# PuM_Arduino_Shield_v2.net
KiCad netlist of a schematic drawn in EAGLE
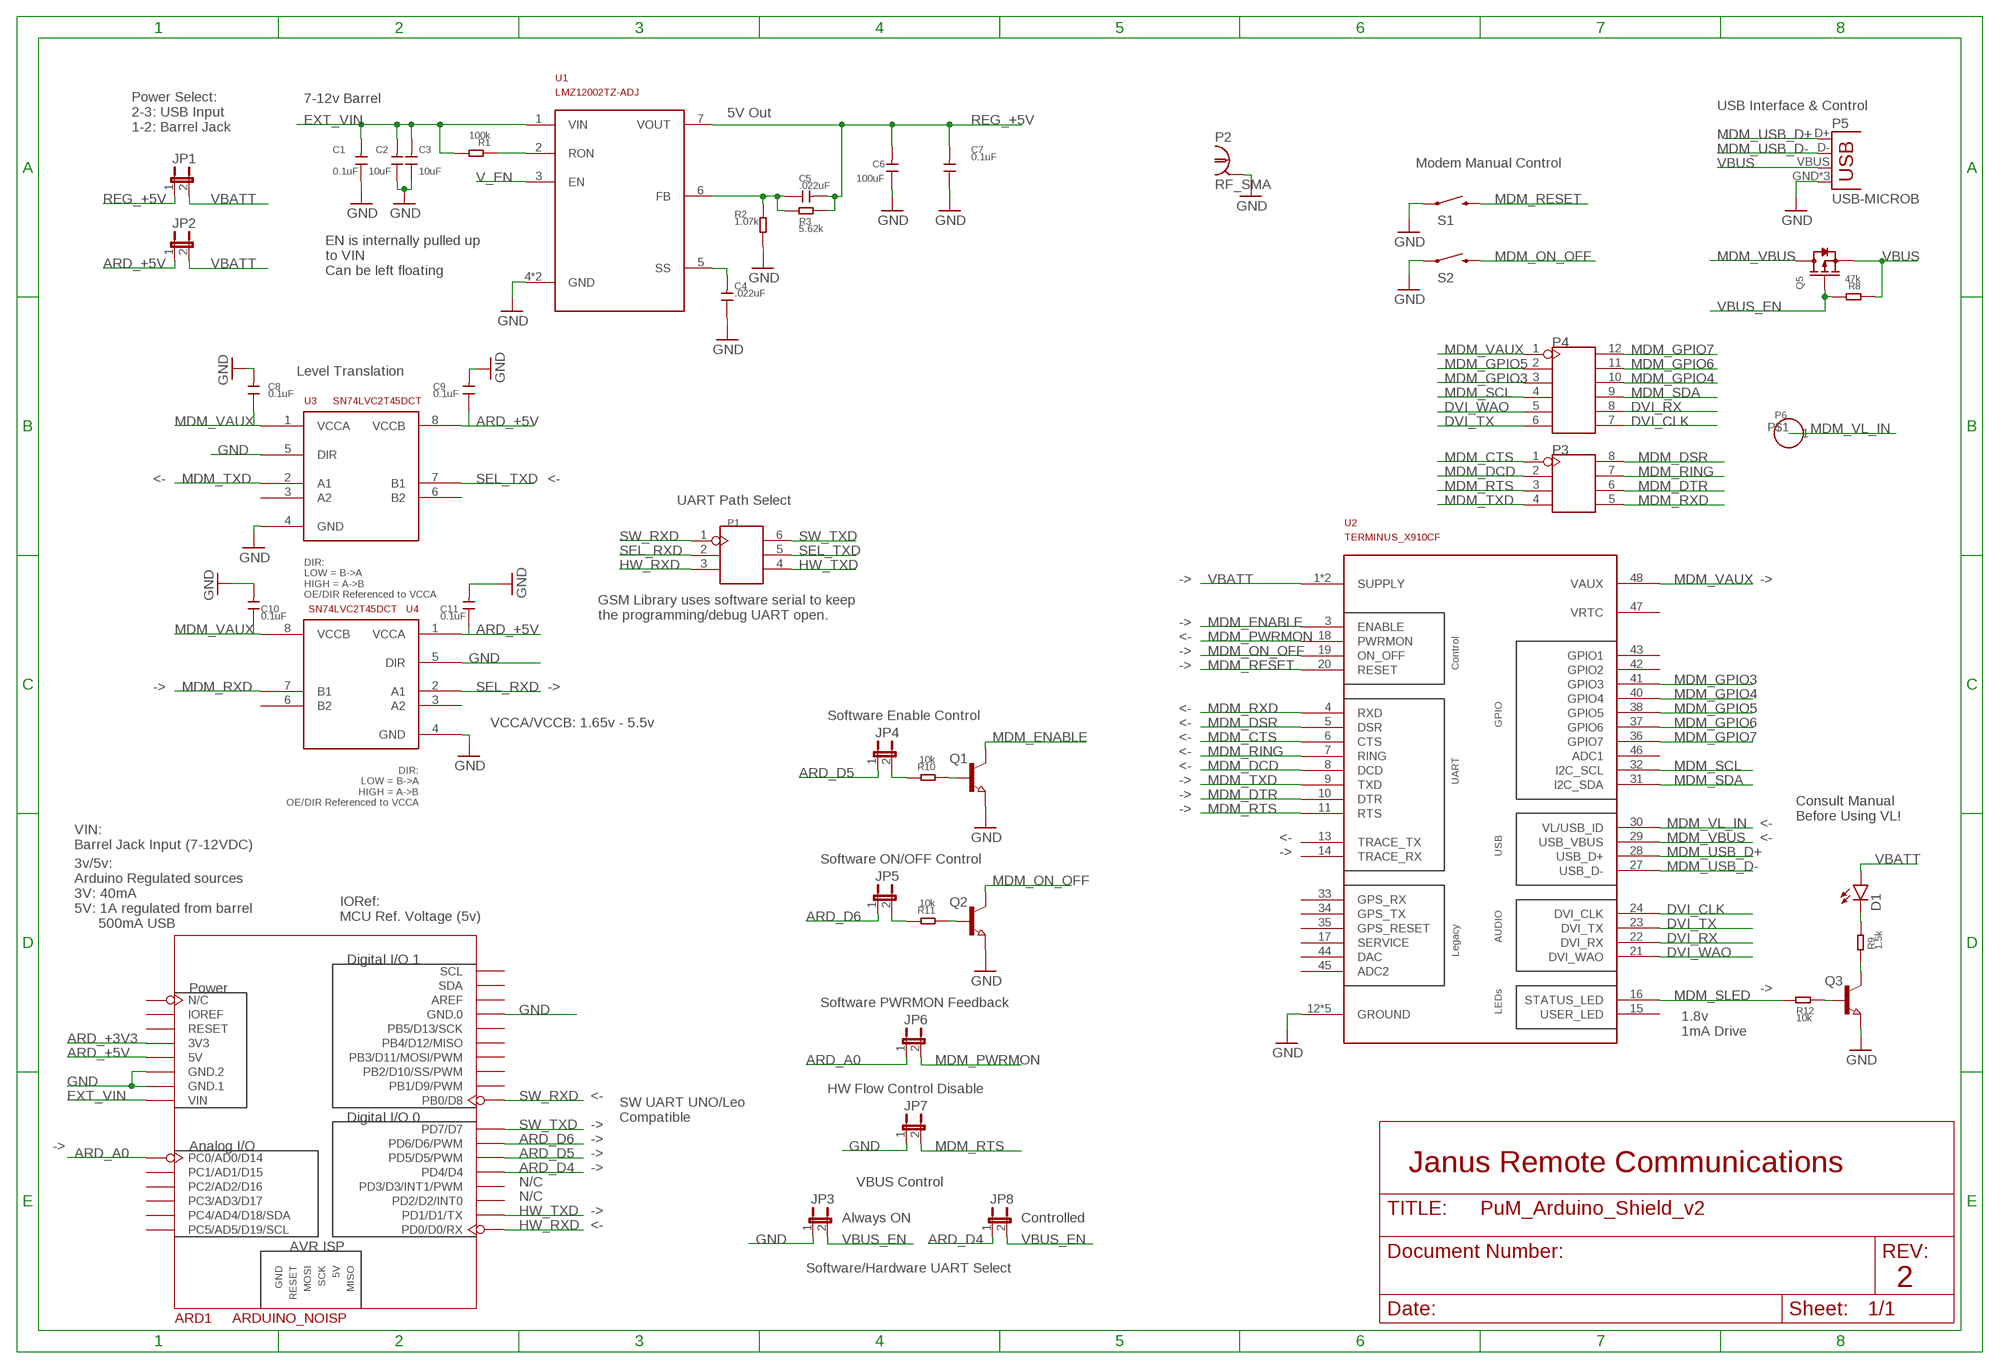
[diagram p0: schematic, sheet 1]

(export (version "E")
  (design (tool "Eeschema 10.0.6"))
  (components
    (comp (ref "ARD1")
      (value "ARDUINO_NOISP")
      (footprint "eagle-import:ARDUINO_NOISP")
      (libsource (lib "eagle-import") (part "ARDUINO_NOISP"))
    )
    (comp (ref "C1")
      (value "0.1uF")
      (footprint "eagle-import:C0402")
      (libsource (lib "eagle-import") (part "C-0402"))
    )
    (comp (ref "C2")
      (value "10uF")
      (footprint "eagle-import:C0805")
      (libsource (lib "eagle-import") (part "C-0805"))
    )
    (comp (ref "C3")
      (value "10uF")
      (footprint "eagle-import:C0805")
      (libsource (lib "eagle-import") (part "C-0805"))
    )
    (comp (ref "C4")
      (value ".022uF")
      (footprint "eagle-import:C0402")
      (libsource (lib "eagle-import") (part "C-0402"))
    )
    (comp (ref "C5")
      (value ".022uF")
      (footprint "eagle-import:C0402")
      (libsource (lib "eagle-import") (part "C-0402"))
    )
    (comp (ref "C6")
      (value "100uF")
      (footprint "eagle-import:C1206")
      (libsource (lib "eagle-import") (part "C-1206"))
    )
    (comp (ref "C7")
      (value "0.1uF")
      (footprint "eagle-import:C0402")
      (libsource (lib "eagle-import") (part "C-0402"))
    )
    (comp (ref "C8")
      (value "0.1uF")
      (footprint "eagle-import:C0402")
      (libsource (lib "eagle-import") (part "C-0402"))
    )
    (comp (ref "C9")
      (value "0.1uF")
      (footprint "eagle-import:C0402")
      (libsource (lib "eagle-import") (part "C-0402"))
    )
    (comp (ref "C10")
      (value "0.1uF")
      (footprint "eagle-import:C0402")
      (libsource (lib "eagle-import") (part "C-0402"))
    )
    (comp (ref "C11")
      (value "0.1uF")
      (footprint "eagle-import:C0402")
      (libsource (lib "eagle-import") (part "C-0402"))
    )
    (comp (ref "D1")
      (value "LED0603")
      (footprint "eagle-import:LED-0603")
      (libsource (lib "eagle-import") (part "LED0603"))
    )
    (comp (ref "JP1")
      (value "JUMPER-2SMD-NC")
      (footprint "eagle-import:SJ_2S")
      (libsource (lib "eagle-import") (part "JUMPER-2SMD-NC"))
    )
    (comp (ref "JP2")
      (value "JUMPER-2SMD-NO")
      (footprint "eagle-import:SJ_2S-NO")
      (libsource (lib "eagle-import") (part "JUMPER-2SMD-NO"))
    )
    (comp (ref "JP3")
      (value "JUMPER-2SMD-NO")
      (footprint "eagle-import:SJ_2S-NO")
      (libsource (lib "eagle-import") (part "JUMPER-2SMD-NO"))
    )
    (comp (ref "JP4")
      (value "JUMPER-2SMD-NC")
      (footprint "eagle-import:SJ_2S")
      (libsource (lib "eagle-import") (part "JUMPER-2SMD-NC"))
    )
    (comp (ref "JP5")
      (value "JUMPER-2SMD-NC")
      (footprint "eagle-import:SJ_2S")
      (libsource (lib "eagle-import") (part "JUMPER-2SMD-NC"))
    )
    (comp (ref "JP6")
      (value "JUMPER-2SMD-NC")
      (footprint "eagle-import:SJ_2S")
      (libsource (lib "eagle-import") (part "JUMPER-2SMD-NC"))
    )
    (comp (ref "JP7")
      (value "JUMPER-2SMD-NC")
      (footprint "eagle-import:SJ_2S")
      (libsource (lib "eagle-import") (part "JUMPER-2SMD-NC"))
    )
    (comp (ref "JP8")
      (value "JUMPER-2SMD-NC")
      (footprint "eagle-import:SJ_2S")
      (libsource (lib "eagle-import") (part "JUMPER-2SMD-NC"))
    )
    (comp (ref "P1")
      (value "HEADER-2X3P-2.54")
      (footprint "eagle-import:2X3P-2.54")
      (libsource (lib "eagle-import") (part "HEADER-2X3P-2.54"))
    )
    (comp (ref "P2")
      (value "RF_SMA")
      (footprint "eagle-import:RF_SMA_NOPIN")
      (libsource (lib "eagle-import") (part "RF_SMA"))
    )
    (comp (ref "P3")
      (value "HEADER-2X4P-2.54")
      (footprint "eagle-import:2X4P-2.54")
      (libsource (lib "eagle-import") (part "HEADER-2X4P-2.54"))
    )
    (comp (ref "P4")
      (value "HEADER-2X6P-2.54")
      (footprint "eagle-import:2X6P-2.54")
      (libsource (lib "eagle-import") (part "HEADER-2X6P-2.54"))
    )
    (comp (ref "P5")
      (value "USB-MICROB")
      (footprint "eagle-import:USB-MICROB")
      (libsource (lib "eagle-import") (part "USB-MICROB"))
    )
    (comp (ref "P6")
      (value "HEADER-1P-35")
      (footprint "eagle-import:1P-65_35MIL")
      (libsource (lib "eagle-import") (part "HEADER-1P-35"))
    )
    (comp (ref "Q1")
      (value "NPN-TRANSISTOR_SOT23")
      (footprint "eagle-import:SOT23")
      (libsource (lib "eagle-import") (part "NPN-TRANSISTOR_SOT23"))
    )
    (comp (ref "Q2")
      (value "NPN-TRANSISTOR_SOT23")
      (footprint "eagle-import:SOT23")
      (libsource (lib "eagle-import") (part "NPN-TRANSISTOR_SOT23"))
    )
    (comp (ref "Q3")
      (value "NPN-TRANSISTOR_SOT23")
      (footprint "eagle-import:SOT23")
      (libsource (lib "eagle-import") (part "NPN-TRANSISTOR_SOT23"))
    )
    (comp (ref "Q5")
      (value "MOSFET-P'SI2323CDS/SI2305DS<BR>'")
      (footprint "eagle-import:SOT23")
      (libsource (lib "eagle-import") (part "MOSFET-P'SI2323CDS/SI2305DS{lt}BR{gt}'"))
    )
    (comp (ref "R1")
      (value "100k")
      (footprint "eagle-import:R0402")
      (libsource (lib "eagle-import") (part "R-0402"))
    )
    (comp (ref "R2")
      (value "1.07k")
      (footprint "eagle-import:R0402")
      (libsource (lib "eagle-import") (part "R-0402"))
    )
    (comp (ref "R3")
      (value "5.62k")
      (footprint "eagle-import:R0402")
      (libsource (lib "eagle-import") (part "R-0402"))
    )
    (comp (ref "R8")
      (value "47k")
      (footprint "eagle-import:R0402")
      (libsource (lib "eagle-import") (part "R-0402"))
    )
    (comp (ref "R9")
      (value "1.5k")
      (footprint "eagle-import:R0402")
      (libsource (lib "eagle-import") (part "R-0402"))
    )
    (comp (ref "R10")
      (value "10k")
      (footprint "eagle-import:R0402")
      (libsource (lib "eagle-import") (part "R-0402"))
    )
    (comp (ref "R11")
      (value "10k")
      (footprint "eagle-import:R0402")
      (libsource (lib "eagle-import") (part "R-0402"))
    )
    (comp (ref "R12")
      (value "10k")
      (footprint "eagle-import:R0402")
      (libsource (lib "eagle-import") (part "R-0402"))
    )
    (comp (ref "S1")
      (value "SWITCH-MOMENTARY-2SIDE_EZ")
      (footprint "eagle-import:TACTILE-PTH-SIDEEZ")
      (libsource (lib "eagle-import") (part "SWITCH-MOMENTARY-2SIDE_EZ"))
    )
    (comp (ref "S2")
      (value "SWITCH-MOMENTARY-2SIDE_EZ")
      (footprint "eagle-import:TACTILE-PTH-SIDEEZ")
      (libsource (lib "eagle-import") (part "SWITCH-MOMENTARY-2SIDE_EZ"))
    )
    (comp (ref "U1")
      (value "LMZ12002TZ-ADJ")
      (footprint "eagle-import:TO-PMOD-7")
      (libsource (lib "eagle-import") (part "LMZ12002TZ-ADJ"))
    )
    (comp (ref "U2")
      (value "TERMINUS_X910CF")
      (footprint "eagle-import:X910CF")
      (libsource (lib "eagle-import") (part "TERMINUS_X910CF"))
    )
    (comp (ref "U3")
      (value "SN74LVC2T45DCT")
      (footprint "eagle-import:LSSOP-8")
      (libsource (lib "eagle-import") (part "SN74LVC2T45DCT"))
    )
    (comp (ref "U4")
      (value "SN74LVC2T45DCT")
      (footprint "eagle-import:LSSOP-8")
      (libsource (lib "eagle-import") (part "SN74LVC2T45DCT"))
    )
  )
  (nets
    (net (code "1") (name "/ARD_+3V3") (class "Default")
      (node (ref "ARD1") (pin "3V3") (pinfunction "3V3_3V3") (pintype "bidirectional"))
    )
    (net (code "2") (name "/ARD_+5V") (class "Default")
      (node (ref "ARD1") (pin "5V") (pinfunction "5V_5V") (pintype "bidirectional"))
      (node (ref "C11") (pin "1") (pinfunction "1_1") (pintype "passive"))
      (node (ref "C9") (pin "1") (pinfunction "1_1") (pintype "passive"))
      (node (ref "JP2") (pin "1") (pinfunction "1_1") (pintype "passive"))
      (node (ref "U3") (pin "8") (pinfunction "VCCB_8") (pintype "bidirectional"))
      (node (ref "U4") (pin "1") (pinfunction "VCCA_1") (pintype "bidirectional"))
    )
    (net (code "3") (name "/ARD_A0") (class "Default")
      (node (ref "ARD1") (pin "A0") (pinfunction "PC0/AD0/D14_A0") (pintype "bidirectional"))
      (node (ref "JP6") (pin "1") (pinfunction "1_1") (pintype "passive"))
    )
    (net (code "4") (name "/ARD_D4") (class "Default")
      (node (ref "ARD1") (pin "D4") (pinfunction "PD4/D4_D4") (pintype "bidirectional"))
      (node (ref "JP8") (pin "1") (pinfunction "1_1") (pintype "passive"))
    )
    (net (code "5") (name "/ARD_D5") (class "Default")
      (node (ref "ARD1") (pin "D5") (pinfunction "PD5/D5/PWM_D5") (pintype "bidirectional"))
      (node (ref "JP4") (pin "1") (pinfunction "1_1") (pintype "passive"))
    )
    (net (code "6") (name "/ARD_D6") (class "Default")
      (node (ref "ARD1") (pin "D6") (pinfunction "PD6/D6/PWM_D6") (pintype "bidirectional"))
      (node (ref "JP5") (pin "1") (pinfunction "1_1") (pintype "passive"))
    )
    (net (code "7") (name "/DVI_CLK") (class "Default")
      (node (ref "P4") (pin "7") (pinfunction "7_7") (pintype "bidirectional"))
      (node (ref "U2") (pin "24") (pinfunction "DVI_CLK_24") (pintype "bidirectional"))
    )
    (net (code "8") (name "/DVI_RX") (class "Default")
      (node (ref "P4") (pin "8") (pinfunction "8_8") (pintype "bidirectional"))
      (node (ref "U2") (pin "22") (pinfunction "DVI_RX_22") (pintype "bidirectional"))
    )
    (net (code "9") (name "/DVI_TX") (class "Default")
      (node (ref "P4") (pin "6") (pinfunction "6_6") (pintype "bidirectional"))
      (node (ref "U2") (pin "23") (pinfunction "DVI_TX_23") (pintype "bidirectional"))
    )
    (net (code "10") (name "/DVI_WAO") (class "Default")
      (node (ref "P4") (pin "5") (pinfunction "5_5") (pintype "bidirectional"))
      (node (ref "U2") (pin "21") (pinfunction "DVI_WAO_21") (pintype "bidirectional"))
    )
    (net (code "11") (name "/EXT_VIN") (class "Default")
      (node (ref "ARD1") (pin "VIN") (pinfunction "VIN_VIN") (pintype "bidirectional"))
      (node (ref "C1") (pin "2") (pinfunction "2_2") (pintype "passive"))
      (node (ref "C2") (pin "2") (pinfunction "2_2") (pintype "passive"))
      (node (ref "C3") (pin "2") (pinfunction "2_2") (pintype "passive"))
      (node (ref "R1") (pin "2") (pinfunction "2_2") (pintype "passive"))
      (node (ref "U1") (pin "1") (pinfunction "VIN_1") (pintype "bidirectional"))
    )
    (net (code "12") (name "/HW_RXD") (class "Default")
      (node (ref "ARD1") (pin "D0") (pinfunction "PD0/D0/RX_D0") (pintype "bidirectional"))
      (node (ref "P1") (pin "3") (pinfunction "3_3") (pintype "bidirectional"))
    )
    (net (code "13") (name "/HW_TXD") (class "Default")
      (node (ref "ARD1") (pin "D1") (pinfunction "PD1/D1/TX_D1") (pintype "bidirectional"))
      (node (ref "P1") (pin "4") (pinfunction "4_4") (pintype "bidirectional"))
    )
    (net (code "14") (name "/MDM_CTS") (class "Default")
      (node (ref "P3") (pin "1") (pinfunction "1_1") (pintype "bidirectional"))
      (node (ref "U2") (pin "6") (pinfunction "CTS_6") (pintype "bidirectional"))
    )
    (net (code "15") (name "/MDM_DCD") (class "Default")
      (node (ref "P3") (pin "2") (pinfunction "2_2") (pintype "bidirectional"))
      (node (ref "U2") (pin "8") (pinfunction "DCD_8") (pintype "bidirectional"))
    )
    (net (code "16") (name "/MDM_DSR") (class "Default")
      (node (ref "P3") (pin "8") (pinfunction "8_8") (pintype "bidirectional"))
      (node (ref "U2") (pin "5") (pinfunction "DSR_5") (pintype "bidirectional"))
    )
    (net (code "17") (name "/MDM_DTR") (class "Default")
      (node (ref "P3") (pin "6") (pinfunction "6_6") (pintype "bidirectional"))
      (node (ref "U2") (pin "10") (pinfunction "DTR_10") (pintype "bidirectional"))
    )
    (net (code "18") (name "/MDM_ENABLE") (class "Default")
      (node (ref "Q1") (pin "3") (pinfunction "C_3") (pintype "passive"))
      (node (ref "U2") (pin "3") (pinfunction "ENABLE_3") (pintype "bidirectional"))
    )
    (net (code "19") (name "/MDM_GPIO3") (class "Default")
      (node (ref "P4") (pin "3") (pinfunction "3_3") (pintype "bidirectional"))
      (node (ref "U2") (pin "41") (pinfunction "GPIO3_41") (pintype "bidirectional"))
    )
    (net (code "20") (name "/MDM_GPIO4") (class "Default")
      (node (ref "P4") (pin "10") (pinfunction "10_10") (pintype "bidirectional"))
      (node (ref "U2") (pin "40") (pinfunction "GPIO4_40") (pintype "bidirectional"))
    )
    (net (code "21") (name "/MDM_GPIO5") (class "Default")
      (node (ref "P4") (pin "2") (pinfunction "2_2") (pintype "bidirectional"))
      (node (ref "U2") (pin "38") (pinfunction "GPIO5_38") (pintype "bidirectional"))
    )
    (net (code "22") (name "/MDM_GPIO6") (class "Default")
      (node (ref "P4") (pin "11") (pinfunction "11_11") (pintype "bidirectional"))
      (node (ref "U2") (pin "37") (pinfunction "GPIO6_37") (pintype "bidirectional"))
    )
    (net (code "23") (name "/MDM_GPIO7") (class "Default")
      (node (ref "P4") (pin "12") (pinfunction "12_12") (pintype "bidirectional"))
      (node (ref "U2") (pin "36") (pinfunction "GPIO7_36") (pintype "bidirectional"))
    )
    (net (code "24") (name "/MDM_ON_OFF") (class "Default")
      (node (ref "Q2") (pin "3") (pinfunction "C_3") (pintype "passive"))
      (node (ref "S2") (pin "2") (pinfunction "2_2") (pintype "passive"))
      (node (ref "U2") (pin "19") (pinfunction "ON_OFF_19") (pintype "bidirectional"))
    )
    (net (code "25") (name "/MDM_PWRMON") (class "Default")
      (node (ref "JP6") (pin "2") (pinfunction "2_2") (pintype "passive"))
      (node (ref "U2") (pin "18") (pinfunction "PWRMON_18") (pintype "bidirectional"))
    )
    (net (code "26") (name "/MDM_RESET") (class "Default")
      (node (ref "S1") (pin "2") (pinfunction "2_2") (pintype "passive"))
      (node (ref "U2") (pin "20") (pinfunction "RESET_20") (pintype "bidirectional"))
    )
    (net (code "27") (name "/MDM_RING") (class "Default")
      (node (ref "P3") (pin "7") (pinfunction "7_7") (pintype "bidirectional"))
      (node (ref "U2") (pin "7") (pinfunction "RING_7") (pintype "bidirectional"))
    )
    (net (code "28") (name "/MDM_RTS") (class "Default")
      (node (ref "JP7") (pin "2") (pinfunction "2_2") (pintype "passive"))
      (node (ref "P3") (pin "3") (pinfunction "3_3") (pintype "bidirectional"))
      (node (ref "U2") (pin "11") (pinfunction "RTS_11") (pintype "bidirectional"))
    )
    (net (code "29") (name "/MDM_RXD") (class "Default")
      (node (ref "P3") (pin "5") (pinfunction "5_5") (pintype "bidirectional"))
      (node (ref "U2") (pin "4") (pinfunction "RXD_4") (pintype "bidirectional"))
      (node (ref "U4") (pin "7") (pinfunction "B1_7") (pintype "bidirectional"))
    )
    (net (code "30") (name "/MDM_SCL") (class "Default")
      (node (ref "P4") (pin "4") (pinfunction "4_4") (pintype "bidirectional"))
      (node (ref "U2") (pin "32") (pinfunction "I2C_SCL_32") (pintype "bidirectional"))
    )
    (net (code "31") (name "/MDM_SDA") (class "Default")
      (node (ref "P4") (pin "9") (pinfunction "9_9") (pintype "bidirectional"))
      (node (ref "U2") (pin "31") (pinfunction "I2C_SDA_31") (pintype "bidirectional"))
    )
    (net (code "32") (name "/MDM_SLED") (class "Default")
      (node (ref "R12") (pin "2") (pinfunction "2_2") (pintype "passive"))
      (node (ref "U2") (pin "16") (pinfunction "STATUS_LED_16") (pintype "bidirectional"))
    )
    (net (code "33") (name "/MDM_TXD") (class "Default")
      (node (ref "P3") (pin "4") (pinfunction "4_4") (pintype "bidirectional"))
      (node (ref "U2") (pin "9") (pinfunction "TXD_9") (pintype "bidirectional"))
      (node (ref "U3") (pin "2") (pinfunction "A1_2") (pintype "bidirectional"))
    )
    (net (code "34") (name "/MDM_USB_D+") (class "Default")
      (node (ref "P5") (pin "D+") (pinfunction "D+_D+") (pintype "bidirectional"))
      (node (ref "U2") (pin "28") (pinfunction "USB_D+_28") (pintype "bidirectional"))
    )
    (net (code "35") (name "/MDM_USB_D-") (class "Default")
      (node (ref "P5") (pin "D-") (pinfunction "D-_D-") (pintype "bidirectional"))
      (node (ref "U2") (pin "27") (pinfunction "USB_D-_27") (pintype "bidirectional"))
    )
    (net (code "36") (name "/MDM_VAUX") (class "Default")
      (node (ref "C10") (pin "1") (pinfunction "1_1") (pintype "passive"))
      (node (ref "C8") (pin "1") (pinfunction "1_1") (pintype "passive"))
      (node (ref "P4") (pin "1") (pinfunction "1_1") (pintype "bidirectional"))
      (node (ref "U2") (pin "48") (pinfunction "VAUX_48") (pintype "bidirectional"))
      (node (ref "U3") (pin "1") (pinfunction "VCCA_1") (pintype "bidirectional"))
      (node (ref "U4") (pin "8") (pinfunction "VCCB_8") (pintype "bidirectional"))
    )
    (net (code "37") (name "/MDM_VBUS") (class "Default")
      (node (ref "Q5") (pin "3") (pinfunction "D_3") (pintype "passive"))
      (node (ref "U2") (pin "29") (pinfunction "USB_VBUS_29") (pintype "bidirectional"))
    )
    (net (code "38") (name "/MDM_VL_IN") (class "Default")
      (node (ref "P6") (pin "P$1") (pinfunction "1_P$1") (pintype "bidirectional"))
      (node (ref "U2") (pin "30") (pinfunction "VL/USB_ID_30") (pintype "bidirectional"))
    )
    (net (code "39") (name "/REG_+5V") (class "Default")
      (node (ref "C5") (pin "2") (pinfunction "2_2") (pintype "passive"))
      (node (ref "C6") (pin "2") (pinfunction "2_2") (pintype "passive"))
      (node (ref "C7") (pin "2") (pinfunction "2_2") (pintype "passive"))
      (node (ref "JP1") (pin "1") (pinfunction "1_1") (pintype "passive"))
      (node (ref "R3") (pin "1") (pinfunction "1_1") (pintype "passive"))
      (node (ref "U1") (pin "7") (pinfunction "VOUT_7") (pintype "bidirectional"))
    )
    (net (code "40") (name "/SEL_RXD") (class "Default")
      (node (ref "P1") (pin "2") (pinfunction "2_2") (pintype "bidirectional"))
      (node (ref "U4") (pin "2") (pinfunction "A1_2") (pintype "bidirectional"))
    )
    (net (code "41") (name "/SEL_TXD") (class "Default")
      (node (ref "P1") (pin "5") (pinfunction "5_5") (pintype "bidirectional"))
      (node (ref "U3") (pin "7") (pinfunction "B1_7") (pintype "bidirectional"))
    )
    (net (code "42") (name "/SW_RXD") (class "Default")
      (node (ref "ARD1") (pin "D8") (pinfunction "PB0/D8_D8") (pintype "bidirectional"))
      (node (ref "P1") (pin "1") (pinfunction "1_1") (pintype "bidirectional"))
    )
    (net (code "43") (name "/SW_TXD") (class "Default")
      (node (ref "ARD1") (pin "D7") (pinfunction "PD7/D7_D7") (pintype "bidirectional"))
      (node (ref "P1") (pin "6") (pinfunction "6_6") (pintype "bidirectional"))
    )
    (net (code "44") (name "/VBATT") (class "Default")
      (node (ref "D1") (pin "A") (pinfunction "A_A") (pintype "passive"))
      (node (ref "JP1") (pin "2") (pinfunction "2_2") (pintype "passive"))
      (node (ref "JP2") (pin "2") (pinfunction "2_2") (pintype "passive"))
      (node (ref "U2") (pin "1") (pinfunction "SUPPLY_1") (pintype "bidirectional"))
      (node (ref "U2") (pin "2") (pinfunction "SUPPLY_2") (pintype "bidirectional"))
    )
    (net (code "45") (name "/VBUS") (class "Default")
      (node (ref "P5") (pin "VBUS") (pinfunction "VBUS_VBUS") (pintype "bidirectional"))
      (node (ref "Q5") (pin "2") (pinfunction "S_2") (pintype "passive"))
      (node (ref "R8") (pin "2") (pinfunction "2_2") (pintype "passive"))
    )
    (net (code "46") (name "/VBUS_EN") (class "Default")
      (node (ref "JP3") (pin "2") (pinfunction "2_2") (pintype "passive"))
      (node (ref "JP8") (pin "2") (pinfunction "2_2") (pintype "passive"))
      (node (ref "Q5") (pin "1") (pinfunction "G_1") (pintype "passive"))
      (node (ref "R8") (pin "1") (pinfunction "1_1") (pintype "passive"))
    )
    (net (code "47") (name "/V_EN") (class "Default")
      (node (ref "U1") (pin "3") (pinfunction "EN_3") (pintype "bidirectional"))
    )
    (net (code "48") (name "GND") (class "Default")
      (node (ref "ARD1") (pin "GND0") (pinfunction "GND.0_GND0") (pintype "bidirectional"))
      (node (ref "ARD1") (pin "GND1") (pinfunction "GND.1_GND1") (pintype "bidirectional"))
      (node (ref "ARD1") (pin "GND2") (pinfunction "GND.2_GND2") (pintype "bidirectional"))
      (node (ref "C1") (pin "1") (pinfunction "1_1") (pintype "passive"))
      (node (ref "C10") (pin "2") (pinfunction "2_2") (pintype "passive"))
      (node (ref "C11") (pin "2") (pinfunction "2_2") (pintype "passive"))
      (node (ref "C2") (pin "1") (pinfunction "1_1") (pintype "passive"))
      (node (ref "C3") (pin "1") (pinfunction "1_1") (pintype "passive"))
      (node (ref "C4") (pin "1") (pinfunction "1_1") (pintype "passive"))
      (node (ref "C6") (pin "1") (pinfunction "1_1") (pintype "passive"))
      (node (ref "C7") (pin "1") (pinfunction "1_1") (pintype "passive"))
      (node (ref "C8") (pin "2") (pinfunction "2_2") (pintype "passive"))
      (node (ref "C9") (pin "2") (pinfunction "2_2") (pintype "passive"))
      (node (ref "JP3") (pin "1") (pinfunction "1_1") (pintype "passive"))
      (node (ref "JP7") (pin "1") (pinfunction "1_1") (pintype "passive"))
      (node (ref "P2") (pin "2") (pinfunction "2_2") (pintype "passive"))
      (node (ref "P2") (pin "3") (pinfunction "2_3") (pintype "passive"))
      (node (ref "P2") (pin "4") (pinfunction "2_4") (pintype "passive"))
      (node (ref "P2") (pin "5") (pinfunction "2_5") (pintype "passive"))
      (node (ref "P5") (pin "GND") (pinfunction "GND_GND") (pintype "bidirectional"))
      (node (ref "P5") (pin "MT1") (pinfunction "GND_MT1") (pintype "bidirectional"))
      (node (ref "P5") (pin "MT2") (pinfunction "GND_MT2") (pintype "bidirectional"))
      (node (ref "Q1") (pin "2") (pinfunction "E_2") (pintype "passive"))
      (node (ref "Q2") (pin "2") (pinfunction "E_2") (pintype "passive"))
      (node (ref "Q3") (pin "2") (pinfunction "E_2") (pintype "passive"))
      (node (ref "R2") (pin "2") (pinfunction "2_2") (pintype "passive"))
      (node (ref "S1") (pin "1") (pinfunction "1_1") (pintype "passive"))
      (node (ref "S2") (pin "1") (pinfunction "1_1") (pintype "passive"))
      (node (ref "U1") (pin "4") (pinfunction "GND_4") (pintype "bidirectional"))
      (node (ref "U1") (pin "EP") (pinfunction "GND_EP") (pintype "bidirectional"))
      (node (ref "U2") (pin "12") (pinfunction "GROUND_12") (pintype "bidirectional"))
      (node (ref "U2") (pin "25") (pinfunction "GROUND_25") (pintype "bidirectional"))
      (node (ref "U2") (pin "26") (pinfunction "GROUND_26") (pintype "bidirectional"))
      (node (ref "U2") (pin "39") (pinfunction "GROUND_39") (pintype "bidirectional"))
      (node (ref "U2") (pin "49") (pinfunction "GROUND_49") (pintype "bidirectional"))
      (node (ref "U3") (pin "4") (pinfunction "GND_4") (pintype "bidirectional"))
      (node (ref "U3") (pin "5") (pinfunction "DIR_5") (pintype "bidirectional"))
      (node (ref "U4") (pin "4") (pinfunction "GND_4") (pintype "bidirectional"))
      (node (ref "U4") (pin "5") (pinfunction "DIR_5") (pintype "bidirectional"))
    )
    (net (code "49") (name "Net-(D1-PadC)") (class "Default")
      (node (ref "D1") (pin "C") (pinfunction "C_C") (pintype "passive"))
      (node (ref "R9") (pin "1") (pinfunction "1_1") (pintype "passive"))
    )
    (net (code "50") (name "Net-(JP4-Pad2)") (class "Default")
      (node (ref "JP4") (pin "2") (pinfunction "2_2") (pintype "passive"))
      (node (ref "R10") (pin "1") (pinfunction "1_1") (pintype "passive"))
    )
    (net (code "51") (name "Net-(JP5-Pad2)") (class "Default")
      (node (ref "JP5") (pin "2") (pinfunction "2_2") (pintype "passive"))
      (node (ref "R11") (pin "1") (pinfunction "1_1") (pintype "passive"))
    )
    (net (code "52") (name "Net-(Q1-B)") (class "Default")
      (node (ref "Q1") (pin "1") (pinfunction "B_1") (pintype "passive"))
      (node (ref "R10") (pin "2") (pinfunction "2_2") (pintype "passive"))
    )
    (net (code "53") (name "Net-(Q2-B)") (class "Default")
      (node (ref "Q2") (pin "1") (pinfunction "B_1") (pintype "passive"))
      (node (ref "R11") (pin "2") (pinfunction "2_2") (pintype "passive"))
    )
    (net (code "54") (name "Net-(Q3-B)") (class "Default")
      (node (ref "Q3") (pin "1") (pinfunction "B_1") (pintype "passive"))
      (node (ref "R12") (pin "1") (pinfunction "1_1") (pintype "passive"))
    )
    (net (code "55") (name "Net-(Q3-C)") (class "Default")
      (node (ref "Q3") (pin "3") (pinfunction "C_3") (pintype "passive"))
      (node (ref "R9") (pin "2") (pinfunction "2_2") (pintype "passive"))
    )
    (net (code "56") (name "Net-(U1-FB)") (class "Default")
      (node (ref "C5") (pin "1") (pinfunction "1_1") (pintype "passive"))
      (node (ref "R2") (pin "1") (pinfunction "1_1") (pintype "passive"))
      (node (ref "R3") (pin "2") (pinfunction "2_2") (pintype "passive"))
      (node (ref "U1") (pin "6") (pinfunction "FB_6") (pintype "bidirectional"))
    )
    (net (code "57") (name "Net-(U1-RON)") (class "Default")
      (node (ref "R1") (pin "1") (pinfunction "1_1") (pintype "passive"))
      (node (ref "U1") (pin "2") (pinfunction "RON_2") (pintype "bidirectional"))
    )
    (net (code "58") (name "Net-(U1-SS)") (class "Default")
      (node (ref "C4") (pin "2") (pinfunction "2_2") (pintype "passive"))
      (node (ref "U1") (pin "5") (pinfunction "SS_5") (pintype "bidirectional"))
    )
    (net (code "59") (name "unconnected-(ARD1-PB1{slash}D9{slash}PWM-PadD9)") (class "Default")
      (node (ref "ARD1") (pin "D9") (pinfunction "PB1/D9/PWM_D9") (pintype "bidirectional"))
    )
    (net (code "60") (name "unconnected-(ARD1-PB2{slash}D10{slash}SS{slash}PWM-PadD10)") (class "Default")
      (node (ref "ARD1") (pin "D10") (pinfunction "PB2/D10/SS/PWM_D10") (pintype "bidirectional"))
    )
    (net (code "61") (name "unconnected-(ARD1-PB3{slash}D11{slash}MOSI{slash}PWM-PadD11)") (class "Default")
      (node (ref "ARD1") (pin "D11") (pinfunction "PB3/D11/MOSI/PWM_D11") (pintype "bidirectional"))
    )
    (net (code "62") (name "unconnected-(ARD1-PB4{slash}D12{slash}MISO-PadD12)") (class "Default")
      (node (ref "ARD1") (pin "D12") (pinfunction "PB4/D12/MISO_D12") (pintype "bidirectional"))
    )
    (net (code "63") (name "unconnected-(ARD1-PB5{slash}D13{slash}SCK-PadD13)") (class "Default")
      (node (ref "ARD1") (pin "D13") (pinfunction "PB5/D13/SCK_D13") (pintype "bidirectional"))
    )
    (net (code "64") (name "unconnected-(ARD1-PC1{slash}AD1{slash}D15-PadA1)") (class "Default")
      (node (ref "ARD1") (pin "A1") (pinfunction "PC1/AD1/D15_A1") (pintype "bidirectional"))
    )
    (net (code "65") (name "unconnected-(ARD1-PC2{slash}AD2{slash}D16-PadA2)") (class "Default")
      (node (ref "ARD1") (pin "A2") (pinfunction "PC2/AD2/D16_A2") (pintype "bidirectional"))
    )
    (net (code "66") (name "unconnected-(ARD1-PC3{slash}AD3{slash}D17-PadA3)") (class "Default")
      (node (ref "ARD1") (pin "A3") (pinfunction "PC3/AD3/D17_A3") (pintype "bidirectional"))
    )
    (net (code "67") (name "unconnected-(ARD1-PC4{slash}AD4{slash}D18{slash}SDA-PadA4)") (class "Default")
      (node (ref "ARD1") (pin "A4") (pinfunction "PC4/AD4/D18/SDA_A4") (pintype "bidirectional"))
    )
    (net (code "68") (name "unconnected-(ARD1-PC5{slash}AD5{slash}D19{slash}SCL-PadA5)") (class "Default")
      (node (ref "ARD1") (pin "A5") (pinfunction "PC5/AD5/D19/SCL_A5") (pintype "bidirectional"))
    )
    (net (code "69") (name "unconnected-(ARD1-PD2{slash}D2{slash}INT0-PadD2)") (class "Default")
      (node (ref "ARD1") (pin "D2") (pinfunction "PD2/D2/INT0_D2") (pintype "bidirectional"))
    )
    (net (code "70") (name "unconnected-(ARD1-PD3{slash}D3{slash}INT1{slash}PWM-PadD3)") (class "Default")
      (node (ref "ARD1") (pin "D3") (pinfunction "PD3/D3/INT1/PWM_D3") (pintype "bidirectional"))
    )
    (net (code "71") (name "unconnected-(ARD1-PadAREF)") (class "Default")
      (node (ref "ARD1") (pin "AREF") (pinfunction "AREF_AREF") (pintype "bidirectional"))
    )
    (net (code "72") (name "unconnected-(ARD1-PadIOREF)") (class "Default")
      (node (ref "ARD1") (pin "IOREF") (pinfunction "IOREF_IOREF") (pintype "bidirectional"))
    )
    (net (code "73") (name "unconnected-(ARD1-PadN{slash}C)") (class "Default")
      (node (ref "ARD1") (pin "N/C") (pinfunction "N/C_N/C") (pintype "bidirectional"))
    )
    (net (code "74") (name "unconnected-(ARD1-PadSCL)") (class "Default")
      (node (ref "ARD1") (pin "SCL") (pinfunction "SCL_SCL") (pintype "bidirectional"))
    )
    (net (code "75") (name "unconnected-(ARD1-PadSDA)") (class "Default")
      (node (ref "ARD1") (pin "SDA") (pinfunction "SDA_SDA") (pintype "bidirectional"))
    )
    (net (code "76") (name "unconnected-(ARD1-RESET-PadRST)") (class "Default")
      (node (ref "ARD1") (pin "RST") (pinfunction "RESET_RST") (pintype "bidirectional"))
    )
    (net (code "77") (name "unconnected-(U2-ADC1-Pad46)") (class "Default")
      (node (ref "U2") (pin "46") (pinfunction "ADC1_46") (pintype "bidirectional"))
    )
    (net (code "78") (name "unconnected-(U2-ADC2-Pad45)") (class "Default")
      (node (ref "U2") (pin "45") (pinfunction "ADC2_45") (pintype "bidirectional"))
    )
    (net (code "79") (name "unconnected-(U2-DAC-Pad44)") (class "Default")
      (node (ref "U2") (pin "44") (pinfunction "DAC_44") (pintype "bidirectional"))
    )
    (net (code "80") (name "unconnected-(U2-GPIO1-Pad43)") (class "Default")
      (node (ref "U2") (pin "43") (pinfunction "GPIO1_43") (pintype "bidirectional"))
    )
    (net (code "81") (name "unconnected-(U2-GPIO2-Pad42)") (class "Default")
      (node (ref "U2") (pin "42") (pinfunction "GPIO2_42") (pintype "bidirectional"))
    )
    (net (code "82") (name "unconnected-(U2-GPS_RESET-Pad35)") (class "Default")
      (node (ref "U2") (pin "35") (pinfunction "GPS_RESET_35") (pintype "bidirectional"))
    )
    (net (code "83") (name "unconnected-(U2-GPS_RX-Pad33)") (class "Default")
      (node (ref "U2") (pin "33") (pinfunction "GPS_RX_33") (pintype "bidirectional"))
    )
    (net (code "84") (name "unconnected-(U2-GPS_TX-Pad34)") (class "Default")
      (node (ref "U2") (pin "34") (pinfunction "GPS_TX_34") (pintype "bidirectional"))
    )
    (net (code "85") (name "unconnected-(U2-SERVICE-Pad17)") (class "Default")
      (node (ref "U2") (pin "17") (pinfunction "SERVICE_17") (pintype "bidirectional"))
    )
    (net (code "86") (name "unconnected-(U2-TRACE_RX-Pad14)") (class "Default")
      (node (ref "U2") (pin "14") (pinfunction "TRACE_RX_14") (pintype "bidirectional"))
    )
    (net (code "87") (name "unconnected-(U2-TRACE_TX-Pad13)") (class "Default")
      (node (ref "U2") (pin "13") (pinfunction "TRACE_TX_13") (pintype "bidirectional"))
    )
    (net (code "88") (name "unconnected-(U2-USER_LED-Pad15)") (class "Default")
      (node (ref "U2") (pin "15") (pinfunction "USER_LED_15") (pintype "bidirectional"))
    )
    (net (code "89") (name "unconnected-(U2-VRTC-Pad47)") (class "Default")
      (node (ref "U2") (pin "47") (pinfunction "VRTC_47") (pintype "bidirectional"))
    )
    (net (code "90") (name "unconnected-(U3-A2-Pad3)") (class "Default")
      (node (ref "U3") (pin "3") (pinfunction "A2_3") (pintype "bidirectional"))
    )
    (net (code "91") (name "unconnected-(U3-B2-Pad6)") (class "Default")
      (node (ref "U3") (pin "6") (pinfunction "B2_6") (pintype "bidirectional"))
    )
    (net (code "92") (name "unconnected-(U4-A2-Pad3)") (class "Default")
      (node (ref "U4") (pin "3") (pinfunction "A2_3") (pintype "bidirectional"))
    )
    (net (code "93") (name "unconnected-(U4-B2-Pad6)") (class "Default")
      (node (ref "U4") (pin "6") (pinfunction "B2_6") (pintype "bidirectional"))
    )
  )
)
